# MIPI_Interface_and_Parallel_Display_Inte.net
KiCad netlist of a schematic drawn in Altium Designer
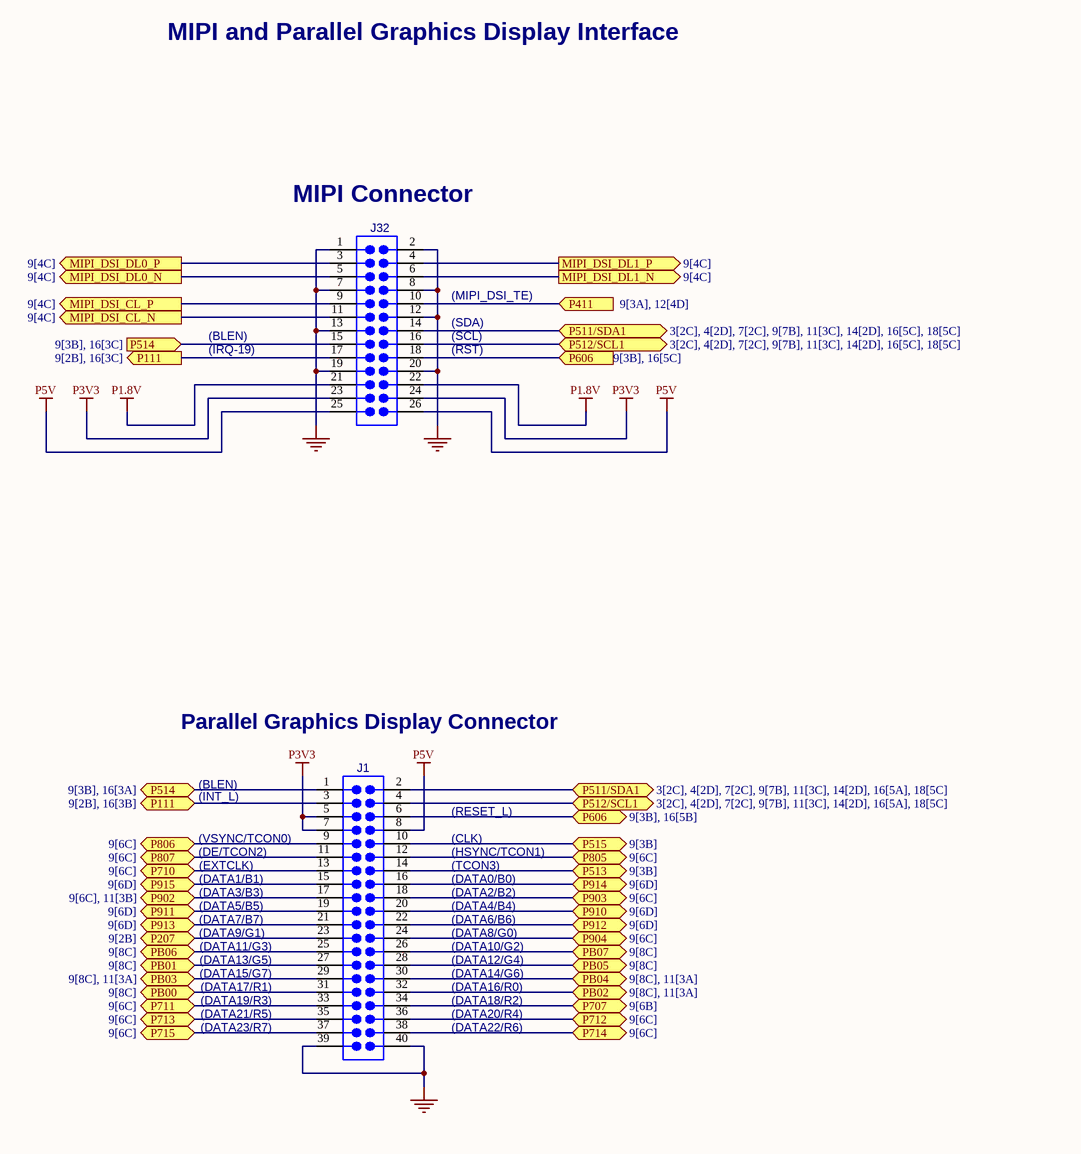
[diagram p0: MIPI Interface and Parallel Display Interface.SchDoc]

(export (version "E")
  (design (tool "Eeschema 10.0.6"))
  (components
    (comp (ref "J1")
      (value "95157-240LF")
      (footprint "amp_95157-240LF")
      (description "Header,40way,2row,vertical,2.54mm,SMT")
      (libsource (lib "ek-ra8d2_mp - Customer") (part "CON_040"))
    )
    (comp (ref "J32")
      (value "CON_026")
      (footprint "sam_ERF8-013-05.0-L-DV-TR")
      (description "Edge Rate Rugged High Speed Socket/Terminal Strip")
      (libsource (lib "ek-ra8d2_mp - Customer") (part "CON_026"))
    )
  )
  (nets
    (net (code "1") (name "/MIPI_DSI_CL_N") (class "Default")
      (node (ref "J32") (pin "11") (pinfunction "11_11") (pintype "passive"))
    )
    (net (code "2") (name "/MIPI_DSI_CL_P") (class "Default")
      (node (ref "J32") (pin "9") (pinfunction "9_9") (pintype "passive"))
    )
    (net (code "3") (name "/MIPI_DSI_DL0_N") (class "Default")
      (node (ref "J32") (pin "5") (pinfunction "5_5") (pintype "passive"))
    )
    (net (code "4") (name "/MIPI_DSI_DL0_P") (class "Default")
      (node (ref "J32") (pin "3") (pinfunction "3_3") (pintype "passive"))
    )
    (net (code "5") (name "/MIPI_DSI_DL1_N") (class "Default")
      (node (ref "J32") (pin "6") (pinfunction "6_6") (pintype "passive"))
    )
    (net (code "6") (name "/MIPI_DSI_DL1_P") (class "Default")
      (node (ref "J32") (pin "4") (pinfunction "4_4") (pintype "passive"))
    )
    (net (code "7") (name "/P111") (class "Default")
      (node (ref "J1") (pin "3") (pinfunction "3_3") (pintype "passive"))
      (node (ref "J32") (pin "17") (pinfunction "17_17") (pintype "passive"))
    )
    (net (code "8") (name "/P207") (class "Default")
      (node (ref "J1") (pin "23") (pinfunction "23_23") (pintype "passive"))
    )
    (net (code "9") (name "/P411") (class "Default")
      (node (ref "J32") (pin "10") (pinfunction "10_10") (pintype "passive"))
    )
    (net (code "10") (name "/P511{slash}SDA1") (class "Default")
      (node (ref "J1") (pin "2") (pinfunction "2_2") (pintype "passive"))
      (node (ref "J32") (pin "14") (pinfunction "14_14") (pintype "passive"))
    )
    (net (code "11") (name "/P512{slash}SCL1") (class "Default")
      (node (ref "J1") (pin "4") (pinfunction "4_4") (pintype "passive"))
      (node (ref "J32") (pin "16") (pinfunction "16_16") (pintype "passive"))
    )
    (net (code "12") (name "/P513") (class "Default")
      (node (ref "J1") (pin "14") (pinfunction "14_14") (pintype "passive"))
    )
    (net (code "13") (name "/P514") (class "Default")
      (node (ref "J1") (pin "1") (pinfunction "1_1") (pintype "passive"))
      (node (ref "J32") (pin "15") (pinfunction "15_15") (pintype "passive"))
    )
    (net (code "14") (name "/P515") (class "Default")
      (node (ref "J1") (pin "10") (pinfunction "10_10") (pintype "passive"))
    )
    (net (code "15") (name "/P606") (class "Default")
      (node (ref "J1") (pin "6") (pinfunction "6_6") (pintype "passive"))
      (node (ref "J32") (pin "18") (pinfunction "18_18") (pintype "passive"))
    )
    (net (code "16") (name "/P707") (class "Default")
      (node (ref "J1") (pin "34") (pinfunction "34_34") (pintype "passive"))
    )
    (net (code "17") (name "/P710") (class "Default")
      (node (ref "J1") (pin "13") (pinfunction "13_13") (pintype "passive"))
    )
    (net (code "18") (name "/P711") (class "Default")
      (node (ref "J1") (pin "33") (pinfunction "33_33") (pintype "passive"))
    )
    (net (code "19") (name "/P712") (class "Default")
      (node (ref "J1") (pin "36") (pinfunction "36_36") (pintype "passive"))
    )
    (net (code "20") (name "/P713") (class "Default")
      (node (ref "J1") (pin "35") (pinfunction "35_35") (pintype "passive"))
    )
    (net (code "21") (name "/P714") (class "Default")
      (node (ref "J1") (pin "38") (pinfunction "38_38") (pintype "passive"))
    )
    (net (code "22") (name "/P715") (class "Default")
      (node (ref "J1") (pin "37") (pinfunction "37_37") (pintype "passive"))
    )
    (net (code "23") (name "/P805") (class "Default")
      (node (ref "J1") (pin "12") (pinfunction "12_12") (pintype "passive"))
    )
    (net (code "24") (name "/P806") (class "Default")
      (node (ref "J1") (pin "9") (pinfunction "9_9") (pintype "passive"))
    )
    (net (code "25") (name "/P807") (class "Default")
      (node (ref "J1") (pin "11") (pinfunction "11_11") (pintype "passive"))
    )
    (net (code "26") (name "/P902") (class "Default")
      (node (ref "J1") (pin "17") (pinfunction "17_17") (pintype "passive"))
    )
    (net (code "27") (name "/P903") (class "Default")
      (node (ref "J1") (pin "18") (pinfunction "18_18") (pintype "passive"))
    )
    (net (code "28") (name "/P904") (class "Default")
      (node (ref "J1") (pin "24") (pinfunction "24_24") (pintype "passive"))
    )
    (net (code "29") (name "/P910") (class "Default")
      (node (ref "J1") (pin "20") (pinfunction "20_20") (pintype "passive"))
    )
    (net (code "30") (name "/P911") (class "Default")
      (node (ref "J1") (pin "19") (pinfunction "19_19") (pintype "passive"))
    )
    (net (code "31") (name "/P912") (class "Default")
      (node (ref "J1") (pin "22") (pinfunction "22_22") (pintype "passive"))
    )
    (net (code "32") (name "/P913") (class "Default")
      (node (ref "J1") (pin "21") (pinfunction "21_21") (pintype "passive"))
    )
    (net (code "33") (name "/P914") (class "Default")
      (node (ref "J1") (pin "16") (pinfunction "16_16") (pintype "passive"))
    )
    (net (code "34") (name "/P915") (class "Default")
      (node (ref "J1") (pin "15") (pinfunction "15_15") (pintype "passive"))
    )
    (net (code "35") (name "/PB00") (class "Default")
      (node (ref "J1") (pin "31") (pinfunction "31_31") (pintype "passive"))
    )
    (net (code "36") (name "/PB01") (class "Default")
      (node (ref "J1") (pin "27") (pinfunction "27_27") (pintype "passive"))
    )
    (net (code "37") (name "/PB02") (class "Default")
      (node (ref "J1") (pin "32") (pinfunction "32_32") (pintype "passive"))
    )
    (net (code "38") (name "/PB03") (class "Default")
      (node (ref "J1") (pin "29") (pinfunction "29_29") (pintype "passive"))
    )
    (net (code "39") (name "/PB04") (class "Default")
      (node (ref "J1") (pin "30") (pinfunction "30_30") (pintype "passive"))
    )
    (net (code "40") (name "/PB05") (class "Default")
      (node (ref "J1") (pin "28") (pinfunction "28_28") (pintype "passive"))
    )
    (net (code "41") (name "/PB06") (class "Default")
      (node (ref "J1") (pin "25") (pinfunction "25_25") (pintype "passive"))
    )
    (net (code "42") (name "/PB07") (class "Default")
      (node (ref "J1") (pin "26") (pinfunction "26_26") (pintype "passive"))
    )
    (net (code "43") (name "GND") (class "Default")
      (node (ref "J1") (pin "39") (pinfunction "39_39") (pintype "passive"))
      (node (ref "J1") (pin "40") (pinfunction "40_40") (pintype "passive"))
      (node (ref "J32") (pin "1") (pinfunction "1_1") (pintype "passive"))
      (node (ref "J32") (pin "12") (pinfunction "12_12") (pintype "passive"))
      (node (ref "J32") (pin "13") (pinfunction "13_13") (pintype "passive"))
      (node (ref "J32") (pin "19") (pinfunction "19_19") (pintype "passive"))
      (node (ref "J32") (pin "2") (pinfunction "2_2") (pintype "passive"))
      (node (ref "J32") (pin "20") (pinfunction "20_20") (pintype "passive"))
      (node (ref "J32") (pin "7") (pinfunction "7_7") (pintype "passive"))
      (node (ref "J32") (pin "8") (pinfunction "8_8") (pintype "passive"))
    )
    (net (code "44") (name "P1.8V") (class "Default")
      (node (ref "J32") (pin "21") (pinfunction "21_21") (pintype "passive"))
      (node (ref "J32") (pin "22") (pinfunction "22_22") (pintype "passive"))
    )
    (net (code "45") (name "P3V3") (class "Default")
      (node (ref "J1") (pin "5") (pinfunction "5_5") (pintype "passive"))
      (node (ref "J1") (pin "7") (pinfunction "7_7") (pintype "passive"))
      (node (ref "J32") (pin "23") (pinfunction "23_23") (pintype "passive"))
      (node (ref "J32") (pin "24") (pinfunction "24_24") (pintype "passive"))
    )
    (net (code "46") (name "P5V") (class "Default")
      (node (ref "J1") (pin "8") (pinfunction "8_8") (pintype "passive"))
      (node (ref "J32") (pin "25") (pinfunction "25_25") (pintype "passive"))
      (node (ref "J32") (pin "26") (pinfunction "26_26") (pintype "passive"))
    )
  )
)
